# 1_panel.net
KiCad netlist of a schematic drawn in Altium Designer
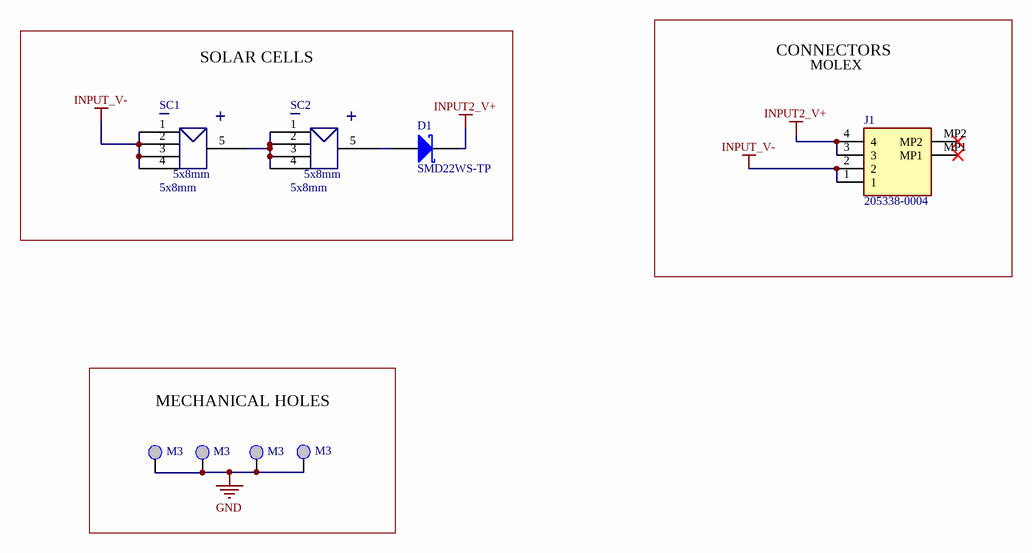
[diagram p0: 1_panel.schdoc]

(export (version "E")
  (design (tool "Eeschema 10.0.6"))
  (components
    (comp (ref "D1")
      (value "SMD22WS-TP")
      (footprint "SOD323F")
      (description "Diode Schottky 20 V 2A Surface Mount SOD-323")
      (libsource (lib "schematics_library_legacy") (part "DIODE_SCHOTTKY_20V_2A_SMD22WS-TP"))
    )
    (comp (ref "J1")
      (value "205338-0004")
      (footprint "MOLEX_4PIN_HEADER")
      (description "Connector")
      (fields (field (name "MOUSER PART NUMBER") "538-205338-0004"))
      (libsource (lib "*") (part "205338-0004"))
    )
    (comp (ref "MEC1")
      (value "M3")
      (footprint "HOLE6x6mm")
      (description "M3 hole")
      (libsource (lib "schematics_library_legacy") (part "M3 hole"))
    )
    (comp (ref "MEC2")
      (value "M3")
      (footprint "HOLE6x6mm")
      (description "M3 hole")
      (libsource (lib "schematics_library_legacy") (part "M3 hole"))
    )
    (comp (ref "MEC3")
      (value "M3")
      (footprint "HOLE6x6mm")
      (description "M3 hole")
      (libsource (lib "schematics_library_legacy") (part "M3 hole"))
    )
    (comp (ref "MEC4")
      (value "M3")
      (footprint "HOLE6x6mm")
      (description "M3 hole")
      (libsource (lib "schematics_library_legacy") (part "M3 hole"))
    )
    (comp (ref "SC1")
      (value "5x8mm")
      (footprint "SOLAR_CELL")
      (fields (field (name "MANUFACTURER") "Yim Space"))
      (libsource (lib "Schlib1") (part "SOLAR CELL"))
    )
    (comp (ref "SC2")
      (value "5x8mm")
      (footprint "SOLAR_CELL")
      (fields (field (name "MANUFACTURER") "Yim Space"))
      (libsource (lib "Schlib1") (part "SOLAR CELL"))
    )
  )
  (nets
    (net (code "1") (name "GND") (class "Default")
      (node (ref "MEC1") (pin "0") (pinfunction "0_0") (pintype "passive"))
      (node (ref "MEC2") (pin "0") (pinfunction "0_0") (pintype "passive"))
      (node (ref "MEC3") (pin "0") (pinfunction "0_0") (pintype "passive"))
      (node (ref "MEC4") (pin "0") (pinfunction "0_0") (pintype "passive"))
    )
    (net (code "2") (name "INPUT2_V+") (class "Default")
      (node (ref "D1") (pin "1") (pinfunction "K_1") (pintype "passive"))
      (node (ref "J1") (pin "3") (pinfunction "3_3") (pintype "passive"))
      (node (ref "J1") (pin "4") (pinfunction "4_4") (pintype "passive"))
    )
    (net (code "3") (name "INPUT_V-") (class "Default")
      (node (ref "J1") (pin "1") (pinfunction "1_1") (pintype "passive"))
      (node (ref "J1") (pin "2") (pinfunction "2_2") (pintype "passive"))
      (node (ref "SC1") (pin "1") (pinfunction "V+_1") (pintype "power_in"))
      (node (ref "SC1") (pin "2") (pinfunction "V-_2") (pintype "power_in"))
      (node (ref "SC1") (pin "3") (pinfunction "3_3") (pintype "passive"))
      (node (ref "SC1") (pin "4") (pinfunction "4_4") (pintype "passive"))
    )
    (net (code "4") (name "Net-(D1-A)") (class "Default")
      (node (ref "D1") (pin "2") (pinfunction "A_2") (pintype "passive"))
      (node (ref "SC2") (pin "5") (pinfunction "5_5") (pintype "passive"))
    )
    (net (code "5") (name "Net-(SC2-V+)") (class "Default")
      (node (ref "SC1") (pin "5") (pinfunction "5_5") (pintype "passive"))
      (node (ref "SC2") (pin "1") (pinfunction "V+_1") (pintype "power_in"))
      (node (ref "SC2") (pin "2") (pinfunction "V-_2") (pintype "power_in"))
      (node (ref "SC2") (pin "3") (pinfunction "3_3") (pintype "passive"))
      (node (ref "SC2") (pin "4") (pinfunction "4_4") (pintype "passive"))
    )
    (net (code "6") (name "unconnected-(J1-PadMP1)") (class "Default")
      (node (ref "J1") (pin "MP1") (pinfunction "MP1_MP1") (pintype "passive+no_connect"))
    )
    (net (code "7") (name "unconnected-(J1-PadMP2)") (class "Default")
      (node (ref "J1") (pin "MP2") (pinfunction "MP2_MP2") (pintype "passive+no_connect"))
    )
  )
)
